# Sheet1.net
KiCad netlist of a schematic drawn in Altium Designer
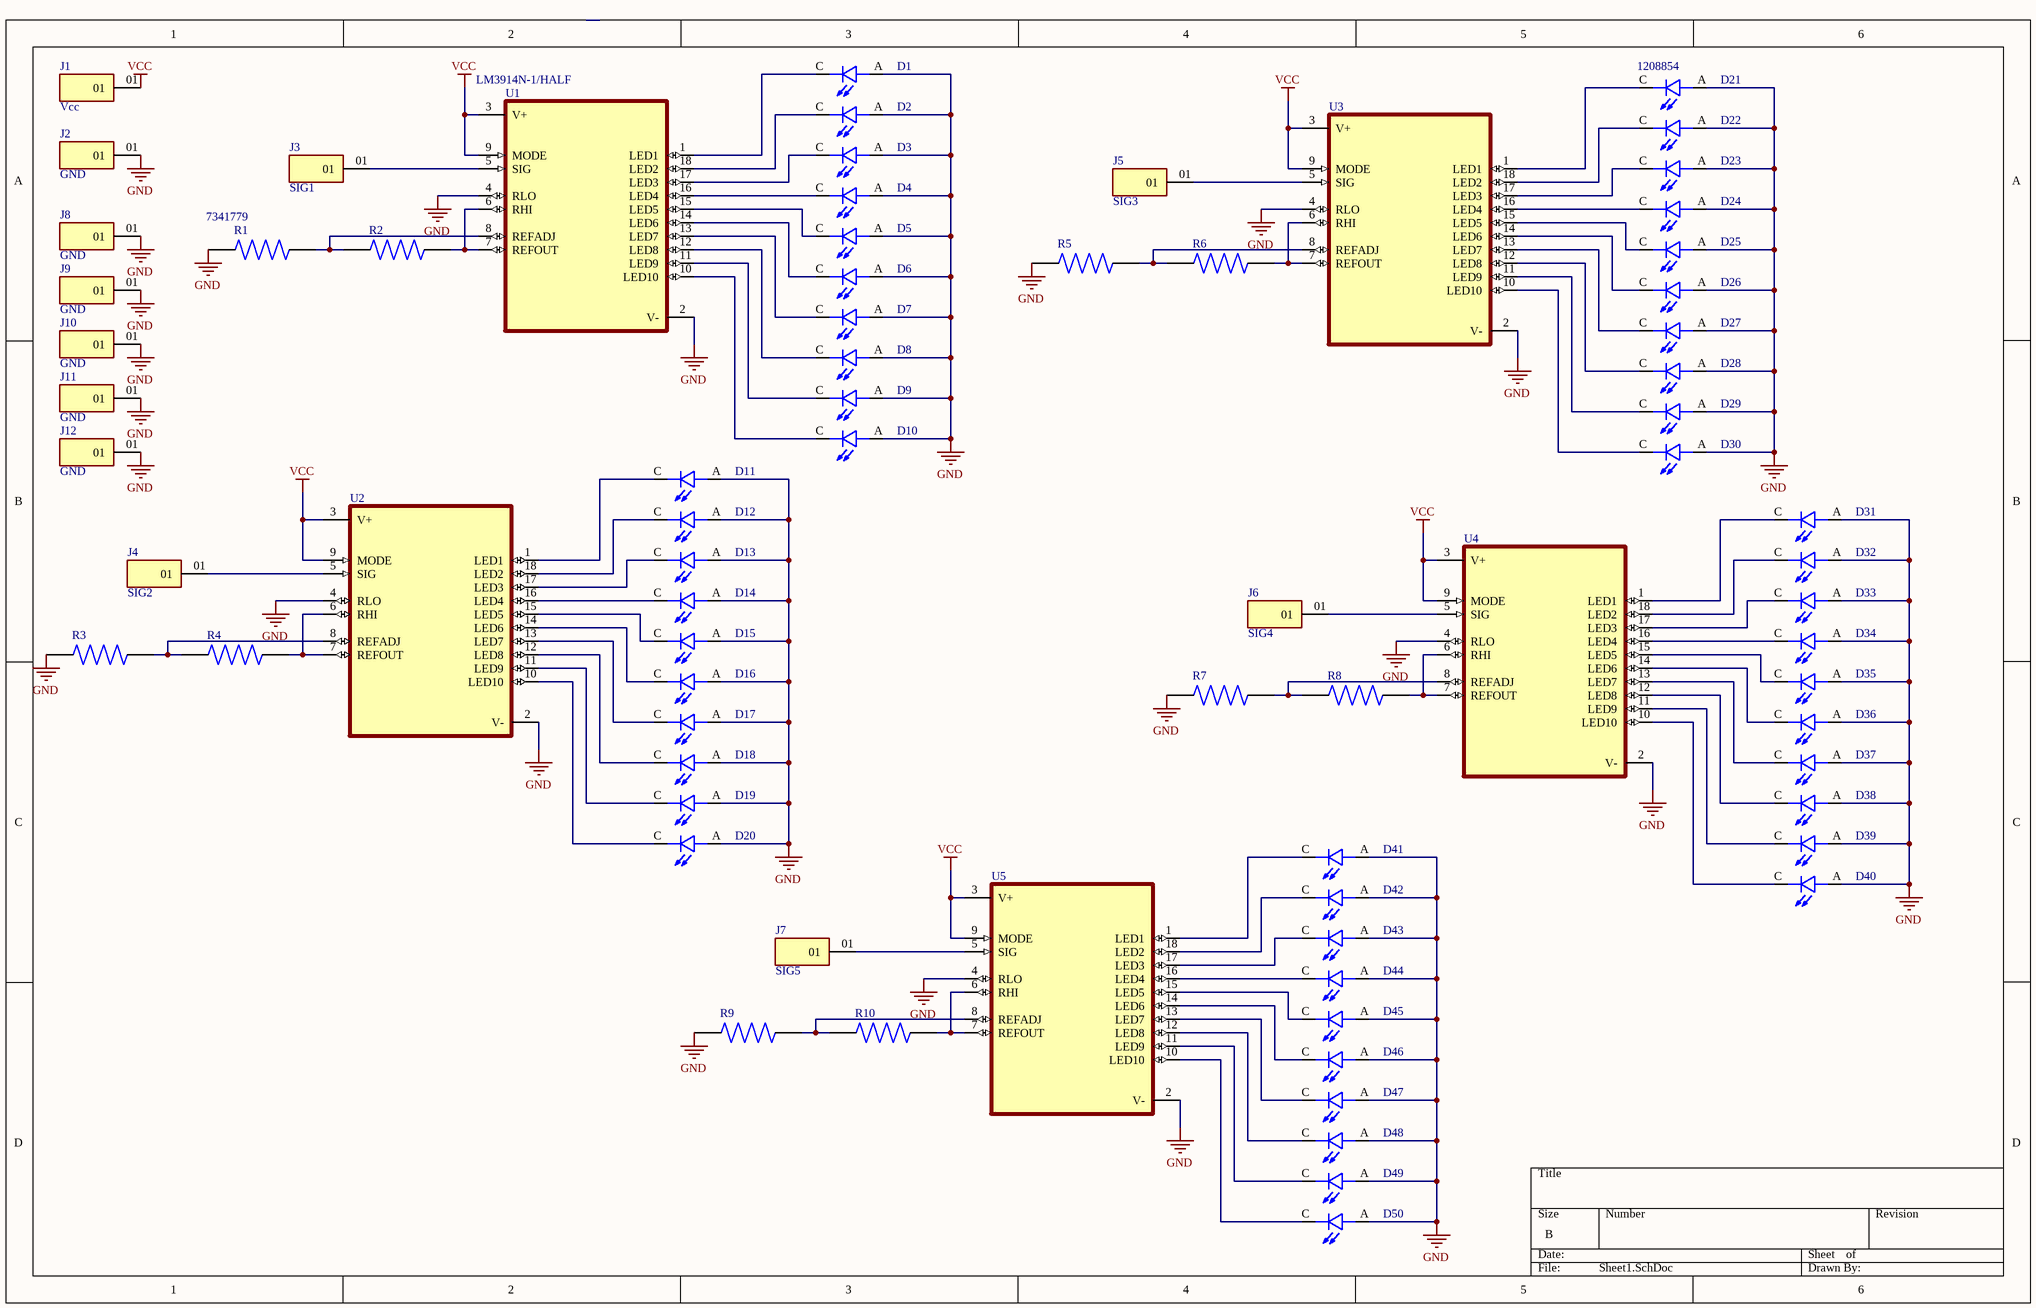
[diagram p0: Sheet1.SchDoc]

(export (version "E")
  (design (tool "Eeschema 10.0.6"))
  (components
    (comp (ref "D1")
      (value "L08R5000Q1")
      (footprint "LEDRD254W57D500H1070")
      (description "LED, Orange, Through Hole, T-1 3/4 (5mm), 30 mA, 2.1 V, 635 nm")
      (libsource (lib "L08R5000Q1") (part "L08R5000Q1"))
    )
    (comp (ref "D2")
      (value "L08R5000Q1")
      (footprint "LEDRD254W57D500H1070")
      (description "LED, Orange, Through Hole, T-1 3/4 (5mm), 30 mA, 2.1 V, 635 nm")
      (libsource (lib "L08R5000Q1") (part "L08R5000Q1"))
    )
    (comp (ref "D3")
      (value "L08R5000Q1")
      (footprint "LEDRD254W57D500H1070")
      (description "LED, Orange, Through Hole, T-1 3/4 (5mm), 30 mA, 2.1 V, 635 nm")
      (libsource (lib "L08R5000Q1") (part "L08R5000Q1"))
    )
    (comp (ref "D4")
      (value "L08R5000Q1")
      (footprint "LEDRD254W57D500H1070")
      (description "LED, Orange, Through Hole, T-1 3/4 (5mm), 30 mA, 2.1 V, 635 nm")
      (libsource (lib "L08R5000Q1") (part "L08R5000Q1"))
    )
    (comp (ref "D5")
      (value "L08R5000Q1")
      (footprint "LEDRD254W57D500H1070")
      (description "LED, Orange, Through Hole, T-1 3/4 (5mm), 30 mA, 2.1 V, 635 nm")
      (libsource (lib "L08R5000Q1") (part "L08R5000Q1"))
    )
    (comp (ref "D6")
      (value "L08R5000Q1")
      (footprint "LEDRD254W57D500H1070")
      (description "LED, Orange, Through Hole, T-1 3/4 (5mm), 30 mA, 2.1 V, 635 nm")
      (libsource (lib "L08R5000Q1") (part "L08R5000Q1"))
    )
    (comp (ref "D7")
      (value "L08R5000Q1")
      (footprint "LEDRD254W57D500H1070")
      (description "LED, Orange, Through Hole, T-1 3/4 (5mm), 30 mA, 2.1 V, 635 nm")
      (libsource (lib "L08R5000Q1") (part "L08R5000Q1"))
    )
    (comp (ref "D8")
      (value "L08R5000Q1")
      (footprint "LEDRD254W57D500H1070")
      (description "LED, Orange, Through Hole, T-1 3/4 (5mm), 30 mA, 2.1 V, 635 nm")
      (libsource (lib "L08R5000Q1") (part "L08R5000Q1"))
    )
    (comp (ref "D9")
      (value "L08R5000Q1")
      (footprint "LEDRD254W57D500H1070")
      (description "LED, Orange, Through Hole, T-1 3/4 (5mm), 30 mA, 2.1 V, 635 nm")
      (libsource (lib "L08R5000Q1") (part "L08R5000Q1"))
    )
    (comp (ref "D10")
      (value "L08R5000Q1")
      (footprint "LEDRD254W57D500H1070")
      (description "LED, Orange, Through Hole, T-1 3/4 (5mm), 30 mA, 2.1 V, 635 nm")
      (libsource (lib "L08R5000Q1") (part "L08R5000Q1"))
    )
    (comp (ref "D11")
      (value "L08R5000Q1")
      (footprint "LEDRD254W57D500H1070")
      (description "LED, Orange, Through Hole, T-1 3/4 (5mm), 30 mA, 2.1 V, 635 nm")
      (libsource (lib "L08R5000Q1") (part "L08R5000Q1"))
    )
    (comp (ref "D12")
      (value "L08R5000Q1")
      (footprint "LEDRD254W57D500H1070")
      (description "LED, Orange, Through Hole, T-1 3/4 (5mm), 30 mA, 2.1 V, 635 nm")
      (libsource (lib "L08R5000Q1") (part "L08R5000Q1"))
    )
    (comp (ref "D13")
      (value "L08R5000Q1")
      (footprint "LEDRD254W57D500H1070")
      (description "LED, Orange, Through Hole, T-1 3/4 (5mm), 30 mA, 2.1 V, 635 nm")
      (libsource (lib "L08R5000Q1") (part "L08R5000Q1"))
    )
    (comp (ref "D14")
      (value "L08R5000Q1")
      (footprint "LEDRD254W57D500H1070")
      (description "LED, Orange, Through Hole, T-1 3/4 (5mm), 30 mA, 2.1 V, 635 nm")
      (libsource (lib "L08R5000Q1") (part "L08R5000Q1"))
    )
    (comp (ref "D15")
      (value "L08R5000Q1")
      (footprint "LEDRD254W57D500H1070")
      (description "LED, Orange, Through Hole, T-1 3/4 (5mm), 30 mA, 2.1 V, 635 nm")
      (libsource (lib "L08R5000Q1") (part "L08R5000Q1"))
    )
    (comp (ref "D16")
      (value "L08R5000Q1")
      (footprint "LEDRD254W57D500H1070")
      (description "LED, Orange, Through Hole, T-1 3/4 (5mm), 30 mA, 2.1 V, 635 nm")
      (libsource (lib "L08R5000Q1") (part "L08R5000Q1"))
    )
    (comp (ref "D17")
      (value "L08R5000Q1")
      (footprint "LEDRD254W57D500H1070")
      (description "LED, Orange, Through Hole, T-1 3/4 (5mm), 30 mA, 2.1 V, 635 nm")
      (libsource (lib "L08R5000Q1") (part "L08R5000Q1"))
    )
    (comp (ref "D18")
      (value "L08R5000Q1")
      (footprint "LEDRD254W57D500H1070")
      (description "LED, Orange, Through Hole, T-1 3/4 (5mm), 30 mA, 2.1 V, 635 nm")
      (libsource (lib "L08R5000Q1") (part "L08R5000Q1"))
    )
    (comp (ref "D19")
      (value "L08R5000Q1")
      (footprint "LEDRD254W57D500H1070")
      (description "LED, Orange, Through Hole, T-1 3/4 (5mm), 30 mA, 2.1 V, 635 nm")
      (libsource (lib "L08R5000Q1") (part "L08R5000Q1"))
    )
    (comp (ref "D20")
      (value "L08R5000Q1")
      (footprint "LEDRD254W57D500H1070")
      (description "LED, Orange, Through Hole, T-1 3/4 (5mm), 30 mA, 2.1 V, 635 nm")
      (libsource (lib "L08R5000Q1") (part "L08R5000Q1"))
    )
    (comp (ref "D21")
      (value "L08R5000Q1")
      (footprint "LEDRD254W57D500H1070")
      (description "LED, Orange, Through Hole, T-1 3/4 (5mm), 30 mA, 2.1 V, 635 nm")
      (fields (field (name "SUPPLIER PART NUMBER 1") "1208854"))
      (libsource (lib "L08R5000Q1") (part "L08R5000Q1"))
    )
    (comp (ref "D22")
      (value "L08R5000Q1")
      (footprint "LEDRD254W57D500H1070")
      (description "LED, Orange, Through Hole, T-1 3/4 (5mm), 30 mA, 2.1 V, 635 nm")
      (libsource (lib "L08R5000Q1") (part "L08R5000Q1"))
    )
    (comp (ref "D23")
      (value "L08R5000Q1")
      (footprint "LEDRD254W57D500H1070")
      (description "LED, Orange, Through Hole, T-1 3/4 (5mm), 30 mA, 2.1 V, 635 nm")
      (libsource (lib "L08R5000Q1") (part "L08R5000Q1"))
    )
    (comp (ref "D24")
      (value "L08R5000Q1")
      (footprint "LEDRD254W57D500H1070")
      (description "LED, Orange, Through Hole, T-1 3/4 (5mm), 30 mA, 2.1 V, 635 nm")
      (libsource (lib "L08R5000Q1") (part "L08R5000Q1"))
    )
    (comp (ref "D25")
      (value "L08R5000Q1")
      (footprint "LEDRD254W57D500H1070")
      (description "LED, Orange, Through Hole, T-1 3/4 (5mm), 30 mA, 2.1 V, 635 nm")
      (libsource (lib "L08R5000Q1") (part "L08R5000Q1"))
    )
    (comp (ref "D26")
      (value "L08R5000Q1")
      (footprint "LEDRD254W57D500H1070")
      (description "LED, Orange, Through Hole, T-1 3/4 (5mm), 30 mA, 2.1 V, 635 nm")
      (libsource (lib "L08R5000Q1") (part "L08R5000Q1"))
    )
    (comp (ref "D27")
      (value "L08R5000Q1")
      (footprint "LEDRD254W57D500H1070")
      (description "LED, Orange, Through Hole, T-1 3/4 (5mm), 30 mA, 2.1 V, 635 nm")
      (libsource (lib "L08R5000Q1") (part "L08R5000Q1"))
    )
    (comp (ref "D28")
      (value "L08R5000Q1")
      (footprint "LEDRD254W57D500H1070")
      (description "LED, Orange, Through Hole, T-1 3/4 (5mm), 30 mA, 2.1 V, 635 nm")
      (libsource (lib "L08R5000Q1") (part "L08R5000Q1"))
    )
    (comp (ref "D29")
      (value "L08R5000Q1")
      (footprint "LEDRD254W57D500H1070")
      (description "LED, Orange, Through Hole, T-1 3/4 (5mm), 30 mA, 2.1 V, 635 nm")
      (libsource (lib "L08R5000Q1") (part "L08R5000Q1"))
    )
    (comp (ref "D30")
      (value "L08R5000Q1")
      (footprint "LEDRD254W57D500H1070")
      (description "LED, Orange, Through Hole, T-1 3/4 (5mm), 30 mA, 2.1 V, 635 nm")
      (libsource (lib "L08R5000Q1") (part "L08R5000Q1"))
    )
    (comp (ref "D31")
      (value "L08R5000Q1")
      (footprint "LEDRD254W57D500H1070")
      (description "LED, Orange, Through Hole, T-1 3/4 (5mm), 30 mA, 2.1 V, 635 nm")
      (libsource (lib "L08R5000Q1") (part "L08R5000Q1"))
    )
    (comp (ref "D32")
      (value "L08R5000Q1")
      (footprint "LEDRD254W57D500H1070")
      (description "LED, Orange, Through Hole, T-1 3/4 (5mm), 30 mA, 2.1 V, 635 nm")
      (libsource (lib "L08R5000Q1") (part "L08R5000Q1"))
    )
    (comp (ref "D33")
      (value "L08R5000Q1")
      (footprint "LEDRD254W57D500H1070")
      (description "LED, Orange, Through Hole, T-1 3/4 (5mm), 30 mA, 2.1 V, 635 nm")
      (libsource (lib "L08R5000Q1") (part "L08R5000Q1"))
    )
    (comp (ref "D34")
      (value "L08R5000Q1")
      (footprint "LEDRD254W57D500H1070")
      (description "LED, Orange, Through Hole, T-1 3/4 (5mm), 30 mA, 2.1 V, 635 nm")
      (libsource (lib "L08R5000Q1") (part "L08R5000Q1"))
    )
    (comp (ref "D35")
      (value "L08R5000Q1")
      (footprint "LEDRD254W57D500H1070")
      (description "LED, Orange, Through Hole, T-1 3/4 (5mm), 30 mA, 2.1 V, 635 nm")
      (libsource (lib "L08R5000Q1") (part "L08R5000Q1"))
    )
    (comp (ref "D36")
      (value "L08R5000Q1")
      (footprint "LEDRD254W57D500H1070")
      (description "LED, Orange, Through Hole, T-1 3/4 (5mm), 30 mA, 2.1 V, 635 nm")
      (libsource (lib "L08R5000Q1") (part "L08R5000Q1"))
    )
    (comp (ref "D37")
      (value "L08R5000Q1")
      (footprint "LEDRD254W57D500H1070")
      (description "LED, Orange, Through Hole, T-1 3/4 (5mm), 30 mA, 2.1 V, 635 nm")
      (libsource (lib "L08R5000Q1") (part "L08R5000Q1"))
    )
    (comp (ref "D38")
      (value "L08R5000Q1")
      (footprint "LEDRD254W57D500H1070")
      (description "LED, Orange, Through Hole, T-1 3/4 (5mm), 30 mA, 2.1 V, 635 nm")
      (libsource (lib "L08R5000Q1") (part "L08R5000Q1"))
    )
    (comp (ref "D39")
      (value "L08R5000Q1")
      (footprint "LEDRD254W57D500H1070")
      (description "LED, Orange, Through Hole, T-1 3/4 (5mm), 30 mA, 2.1 V, 635 nm")
      (libsource (lib "L08R5000Q1") (part "L08R5000Q1"))
    )
    (comp (ref "D40")
      (value "L08R5000Q1")
      (footprint "LEDRD254W57D500H1070")
      (description "LED, Orange, Through Hole, T-1 3/4 (5mm), 30 mA, 2.1 V, 635 nm")
      (libsource (lib "L08R5000Q1") (part "L08R5000Q1"))
    )
    (comp (ref "D41")
      (value "L08R5000Q1")
      (footprint "LEDRD254W57D500H1070")
      (description "LED, Orange, Through Hole, T-1 3/4 (5mm), 30 mA, 2.1 V, 635 nm")
      (libsource (lib "L08R5000Q1") (part "L08R5000Q1"))
    )
    (comp (ref "D42")
      (value "L08R5000Q1")
      (footprint "LEDRD254W57D500H1070")
      (description "LED, Orange, Through Hole, T-1 3/4 (5mm), 30 mA, 2.1 V, 635 nm")
      (libsource (lib "L08R5000Q1") (part "L08R5000Q1"))
    )
    (comp (ref "D43")
      (value "L08R5000Q1")
      (footprint "LEDRD254W57D500H1070")
      (description "LED, Orange, Through Hole, T-1 3/4 (5mm), 30 mA, 2.1 V, 635 nm")
      (libsource (lib "L08R5000Q1") (part "L08R5000Q1"))
    )
    (comp (ref "D44")
      (value "L08R5000Q1")
      (footprint "LEDRD254W57D500H1070")
      (description "LED, Orange, Through Hole, T-1 3/4 (5mm), 30 mA, 2.1 V, 635 nm")
      (libsource (lib "L08R5000Q1") (part "L08R5000Q1"))
    )
    (comp (ref "D45")
      (value "L08R5000Q1")
      (footprint "LEDRD254W57D500H1070")
      (description "LED, Orange, Through Hole, T-1 3/4 (5mm), 30 mA, 2.1 V, 635 nm")
      (libsource (lib "L08R5000Q1") (part "L08R5000Q1"))
    )
    (comp (ref "D46")
      (value "L08R5000Q1")
      (footprint "LEDRD254W57D500H1070")
      (description "LED, Orange, Through Hole, T-1 3/4 (5mm), 30 mA, 2.1 V, 635 nm")
      (libsource (lib "L08R5000Q1") (part "L08R5000Q1"))
    )
    (comp (ref "D47")
      (value "L08R5000Q1")
      (footprint "LEDRD254W57D500H1070")
      (description "LED, Orange, Through Hole, T-1 3/4 (5mm), 30 mA, 2.1 V, 635 nm")
      (libsource (lib "L08R5000Q1") (part "L08R5000Q1"))
    )
    (comp (ref "D48")
      (value "L08R5000Q1")
      (footprint "LEDRD254W57D500H1070")
      (description "LED, Orange, Through Hole, T-1 3/4 (5mm), 30 mA, 2.1 V, 635 nm")
      (libsource (lib "L08R5000Q1") (part "L08R5000Q1"))
    )
    (comp (ref "D49")
      (value "L08R5000Q1")
      (footprint "LEDRD254W57D500H1070")
      (description "LED, Orange, Through Hole, T-1 3/4 (5mm), 30 mA, 2.1 V, 635 nm")
      (libsource (lib "L08R5000Q1") (part "L08R5000Q1"))
    )
    (comp (ref "D50")
      (value "L08R5000Q1")
      (footprint "LEDRD254W57D500H1070")
      (description "LED, Orange, Through Hole, T-1 3/4 (5mm), 30 mA, 2.1 V, 635 nm")
      (libsource (lib "L08R5000Q1") (part "L08R5000Q1"))
    )
    (comp (ref "J1")
      (value "Vcc")
      (footprint "SAMTEC_MTMM-101-XX-X-S-XXX")
      (description "Connector Header position")
      (fields (field (name "MP") "MTMM-101-XX-X-S-XXX"))
      (libsource (lib "MTMM-101-XX-X-S-XXX") (part "MTMM-101-XX-X-S-XXX"))
    )
    (comp (ref "J2")
      (value "GND")
      (footprint "SAMTEC_MTMM-101-XX-X-S-XXX")
      (description "Connector Header position")
      (fields (field (name "MP") "MTMM-101-XX-X-S-XXX"))
      (libsource (lib "MTMM-101-XX-X-S-XXX") (part "MTMM-101-XX-X-S-XXX"))
    )
    (comp (ref "J3")
      (value "SIG1")
      (footprint "SAMTEC_MTMM-101-XX-X-S-XXX")
      (description "Connector Header position")
      (fields (field (name "MP") "MTMM-101-XX-X-S-XXX"))
      (libsource (lib "MTMM-101-XX-X-S-XXX") (part "MTMM-101-XX-X-S-XXX"))
    )
    (comp (ref "J4")
      (value "SIG2")
      (footprint "SAMTEC_MTMM-101-XX-X-S-XXX")
      (description "Connector Header position")
      (fields (field (name "MP") "MTMM-101-XX-X-S-XXX"))
      (libsource (lib "MTMM-101-XX-X-S-XXX") (part "MTMM-101-XX-X-S-XXX"))
    )
    (comp (ref "J5")
      (value "SIG3")
      (footprint "SAMTEC_MTMM-101-XX-X-S-XXX")
      (description "Connector Header position")
      (fields (field (name "MP") "MTMM-101-XX-X-S-XXX"))
      (libsource (lib "MTMM-101-XX-X-S-XXX") (part "MTMM-101-XX-X-S-XXX"))
    )
    (comp (ref "J6")
      (value "SIG4")
      (footprint "SAMTEC_MTMM-101-XX-X-S-XXX")
      (description "Connector Header position")
      (fields (field (name "MP") "MTMM-101-XX-X-S-XXX"))
      (libsource (lib "MTMM-101-XX-X-S-XXX") (part "MTMM-101-XX-X-S-XXX"))
    )
    (comp (ref "J7")
      (value "SIG5")
      (footprint "SAMTEC_MTMM-101-XX-X-S-XXX")
      (description "Connector Header position")
      (fields (field (name "MP") "MTMM-101-XX-X-S-XXX"))
      (libsource (lib "MTMM-101-XX-X-S-XXX") (part "MTMM-101-XX-X-S-XXX"))
    )
    (comp (ref "J8")
      (value "GND")
      (footprint "SAMTEC_MTMM-101-XX-X-S-XXX")
      (description "Connector Header position")
      (fields (field (name "MP") "MTMM-101-XX-X-S-XXX"))
      (libsource (lib "MTMM-101-XX-X-S-XXX") (part "MTMM-101-XX-X-S-XXX"))
    )
    (comp (ref "J9")
      (value "GND")
      (footprint "SAMTEC_MTMM-101-XX-X-S-XXX")
      (description "Connector Header position")
      (fields (field (name "MP") "MTMM-101-XX-X-S-XXX"))
      (libsource (lib "MTMM-101-XX-X-S-XXX") (part "MTMM-101-XX-X-S-XXX"))
    )
    (comp (ref "J10")
      (value "GND")
      (footprint "SAMTEC_MTMM-101-XX-X-S-XXX")
      (description "Connector Header position")
      (fields (field (name "MP") "MTMM-101-XX-X-S-XXX"))
      (libsource (lib "MTMM-101-XX-X-S-XXX") (part "MTMM-101-XX-X-S-XXX"))
    )
    (comp (ref "J11")
      (value "GND")
      (footprint "SAMTEC_MTMM-101-XX-X-S-XXX")
      (description "Connector Header position")
      (fields (field (name "MP") "MTMM-101-XX-X-S-XXX"))
      (libsource (lib "MTMM-101-XX-X-S-XXX") (part "MTMM-101-XX-X-S-XXX"))
    )
    (comp (ref "J12")
      (value "GND")
      (footprint "SAMTEC_MTMM-101-XX-X-S-XXX")
      (description "Connector Header position")
      (fields (field (name "MP") "MTMM-101-XX-X-S-XXX"))
      (libsource (lib "MTMM-101-XX-X-S-XXX") (part "MTMM-101-XX-X-S-XXX"))
    )
    (comp (ref "R1")
      (value "MFR-25FBF52-1K")
      (footprint "RESAD1100W55L680D260")
      (description "1.78 kOhms Â±1% 0.25W, 1/4W Through Hole Resistor Axial - Metal Film")
      (fields (field (name "MF") "Yageo") (field (name "SUPPLIER PART NUMBER 1") "7341779"))
      (libsource (lib "MFR-25FBF52-1K") (part "MFR-25FBF52-1K"))
    )
    (comp (ref "R2")
      (value "MFR-25FBF52-1K")
      (footprint "RESAD1100W55L680D260")
      (description "1.78 kOhms Â±1% 0.25W, 1/4W Through Hole Resistor Axial - Metal Film")
      (fields (field (name "MF") "Yageo"))
      (libsource (lib "MFR-25FBF52-1K") (part "MFR-25FBF52-1K"))
    )
    (comp (ref "R3")
      (value "MFR-25FBF52-1K")
      (footprint "RESAD1100W55L680D260")
      (description "1.78 kOhms Â±1% 0.25W, 1/4W Through Hole Resistor Axial - Metal Film")
      (fields (field (name "MF") "Yageo"))
      (libsource (lib "MFR-25FBF52-1K") (part "MFR-25FBF52-1K"))
    )
    (comp (ref "R4")
      (value "MFR-25FBF52-1K")
      (footprint "RESAD1100W55L680D260")
      (description "1.78 kOhms Â±1% 0.25W, 1/4W Through Hole Resistor Axial - Metal Film")
      (fields (field (name "MF") "Yageo"))
      (libsource (lib "MFR-25FBF52-1K") (part "MFR-25FBF52-1K"))
    )
    (comp (ref "R5")
      (value "MFR-25FBF52-1K")
      (footprint "RESAD1100W55L680D260")
      (description "1.78 kOhms Â±1% 0.25W, 1/4W Through Hole Resistor Axial - Metal Film")
      (fields (field (name "MF") "Yageo"))
      (libsource (lib "MFR-25FBF52-1K") (part "MFR-25FBF52-1K"))
    )
    (comp (ref "R6")
      (value "MFR-25FBF52-1K")
      (footprint "RESAD1100W55L680D260")
      (description "1.78 kOhms Â±1% 0.25W, 1/4W Through Hole Resistor Axial - Metal Film")
      (fields (field (name "MF") "Yageo"))
      (libsource (lib "MFR-25FBF52-1K") (part "MFR-25FBF52-1K"))
    )
    (comp (ref "R7")
      (value "MFR-25FBF52-1K")
      (footprint "RESAD1100W55L680D260")
      (description "1.78 kOhms Â±1% 0.25W, 1/4W Through Hole Resistor Axial - Metal Film")
      (fields (field (name "MF") "Yageo"))
      (libsource (lib "MFR-25FBF52-1K") (part "MFR-25FBF52-1K"))
    )
    (comp (ref "R8")
      (value "MFR-25FBF52-1K")
      (footprint "RESAD1100W55L680D260")
      (description "1.78 kOhms Â±1% 0.25W, 1/4W Through Hole Resistor Axial - Metal Film")
      (fields (field (name "MF") "Yageo"))
      (libsource (lib "MFR-25FBF52-1K") (part "MFR-25FBF52-1K"))
    )
    (comp (ref "R9")
      (value "MFR-25FBF52-1K")
      (footprint "RESAD1100W55L680D260")
      (description "1.78 kOhms Â±1% 0.25W, 1/4W Through Hole Resistor Axial - Metal Film")
      (fields (field (name "MF") "Yageo"))
      (libsource (lib "MFR-25FBF52-1K") (part "MFR-25FBF52-1K"))
    )
    (comp (ref "R10")
      (value "MFR-25FBF52-1K")
      (footprint "RESAD1100W55L680D260")
      (description "1.78 kOhms Â±1% 0.25W, 1/4W Through Hole Resistor Axial - Metal Film")
      (fields (field (name "MF") "Yageo"))
      (libsource (lib "MFR-25FBF52-1K") (part "MFR-25FBF52-1K"))
    )
    (comp (ref "U1")
      (value "LM3914N-1")
      (footprint "DIP952W45P254L2336H533Q18")
      (fields (field (name "SUPPLIER PART NUMBER 1") "LM3914N-1/HALF"))
      (libsource (lib "LM3914N-1") (part "LM3914N-1"))
    )
    (comp (ref "U2")
      (value "LM3914N-1")
      (footprint "DIP952W45P254L2336H533Q18")
      (libsource (lib "LM3914N-1") (part "LM3914N-1"))
    )
    (comp (ref "U3")
      (value "LM3914N-1")
      (footprint "DIP952W45P254L2336H533Q18")
      (libsource (lib "LM3914N-1") (part "LM3914N-1"))
    )
    (comp (ref "U4")
      (value "LM3914N-1")
      (footprint "DIP952W45P254L2336H533Q18")
      (libsource (lib "LM3914N-1") (part "LM3914N-1"))
    )
    (comp (ref "U5")
      (value "LM3914N-1")
      (footprint "DIP952W45P254L2336H533Q18")
      (libsource (lib "LM3914N-1") (part "LM3914N-1"))
    )
  )
  (nets
    (net (code "1") (name "GND") (class "Default")
      (node (ref "D1") (pin "A") (pinfunction "A_A") (pintype "passive"))
      (node (ref "D10") (pin "A") (pinfunction "A_A") (pintype "passive"))
      (node (ref "D11") (pin "A") (pinfunction "A_A") (pintype "passive"))
      (node (ref "D12") (pin "A") (pinfunction "A_A") (pintype "passive"))
      (node (ref "D13") (pin "A") (pinfunction "A_A") (pintype "passive"))
      (node (ref "D14") (pin "A") (pinfunction "A_A") (pintype "passive"))
      (node (ref "D15") (pin "A") (pinfunction "A_A") (pintype "passive"))
      (node (ref "D16") (pin "A") (pinfunction "A_A") (pintype "passive"))
      (node (ref "D17") (pin "A") (pinfunction "A_A") (pintype "passive"))
      (node (ref "D18") (pin "A") (pinfunction "A_A") (pintype "passive"))
      (node (ref "D19") (pin "A") (pinfunction "A_A") (pintype "passive"))
      (node (ref "D2") (pin "A") (pinfunction "A_A") (pintype "passive"))
      (node (ref "D20") (pin "A") (pinfunction "A_A") (pintype "passive"))
      (node (ref "D21") (pin "A") (pinfunction "A_A") (pintype "passive"))
      (node (ref "D22") (pin "A") (pinfunction "A_A") (pintype "passive"))
      (node (ref "D23") (pin "A") (pinfunction "A_A") (pintype "passive"))
      (node (ref "D24") (pin "A") (pinfunction "A_A") (pintype "passive"))
      (node (ref "D25") (pin "A") (pinfunction "A_A") (pintype "passive"))
      (node (ref "D26") (pin "A") (pinfunction "A_A") (pintype "passive"))
      (node (ref "D27") (pin "A") (pinfunction "A_A") (pintype "passive"))
      (node (ref "D28") (pin "A") (pinfunction "A_A") (pintype "passive"))
      (node (ref "D29") (pin "A") (pinfunction "A_A") (pintype "passive"))
      (node (ref "D3") (pin "A") (pinfunction "A_A") (pintype "passive"))
      (node (ref "D30") (pin "A") (pinfunction "A_A") (pintype "passive"))
      (node (ref "D31") (pin "A") (pinfunction "A_A") (pintype "passive"))
      (node (ref "D32") (pin "A") (pinfunction "A_A") (pintype "passive"))
      (node (ref "D33") (pin "A") (pinfunction "A_A") (pintype "passive"))
      (node (ref "D34") (pin "A") (pinfunction "A_A") (pintype "passive"))
      (node (ref "D35") (pin "A") (pinfunction "A_A") (pintype "passive"))
      (node (ref "D36") (pin "A") (pinfunction "A_A") (pintype "passive"))
      (node (ref "D37") (pin "A") (pinfunction "A_A") (pintype "passive"))
      (node (ref "D38") (pin "A") (pinfunction "A_A") (pintype "passive"))
      (node (ref "D39") (pin "A") (pinfunction "A_A") (pintype "passive"))
      (node (ref "D4") (pin "A") (pinfunction "A_A") (pintype "passive"))
      (node (ref "D40") (pin "A") (pinfunction "A_A") (pintype "passive"))
      (node (ref "D41") (pin "A") (pinfunction "A_A") (pintype "passive"))
      (node (ref "D42") (pin "A") (pinfunction "A_A") (pintype "passive"))
      (node (ref "D43") (pin "A") (pinfunction "A_A") (pintype "passive"))
      (node (ref "D44") (pin "A") (pinfunction "A_A") (pintype "passive"))
      (node (ref "D45") (pin "A") (pinfunction "A_A") (pintype "passive"))
      (node (ref "D46") (pin "A") (pinfunction "A_A") (pintype "passive"))
      (node (ref "D47") (pin "A") (pinfunction "A_A") (pintype "passive"))
      (node (ref "D48") (pin "A") (pinfunction "A_A") (pintype "passive"))
      (node (ref "D49") (pin "A") (pinfunction "A_A") (pintype "passive"))
      (node (ref "D5") (pin "A") (pinfunction "A_A") (pintype "passive"))
      (node (ref "D50") (pin "A") (pinfunction "A_A") (pintype "passive"))
      (node (ref "D6") (pin "A") (pinfunction "A_A") (pintype "passive"))
      (node (ref "D7") (pin "A") (pinfunction "A_A") (pintype "passive"))
      (node (ref "D8") (pin "A") (pinfunction "A_A") (pintype "passive"))
      (node (ref "D9") (pin "A") (pinfunction "A_A") (pintype "passive"))
      (node (ref "J10") (pin "01") (pinfunction "01_01") (pintype "passive"))
      (node (ref "J11") (pin "01") (pinfunction "01_01") (pintype "passive"))
      (node (ref "J12") (pin "01") (pinfunction "01_01") (pintype "passive"))
      (node (ref "J2") (pin "01") (pinfunction "01_01") (pintype "passive"))
      (node (ref "J8") (pin "01") (pinfunction "01_01") (pintype "passive"))
      (node (ref "J9") (pin "01") (pinfunction "01_01") (pintype "passive"))
      (node (ref "R1") (pin "1") (pinfunction "1_1") (pintype "passive"))
      (node (ref "R3") (pin "1") (pinfunction "1_1") (pintype "passive"))
      (node (ref "R5") (pin "1") (pinfunction "1_1") (pintype "passive"))
      (node (ref "R7") (pin "1") (pinfunction "1_1") (pintype "passive"))
      (node (ref "R9") (pin "1") (pinfunction "1_1") (pintype "passive"))
      (node (ref "U1") (pin "2") (pinfunction "V-_2") (pintype "power_in"))
      (node (ref "U1") (pin "4") (pinfunction "RLO_4") (pintype "bidirectional"))
      (node (ref "U2") (pin "2") (pinfunction "V-_2") (pintype "power_in"))
      (node (ref "U2") (pin "4") (pinfunction "RLO_4") (pintype "bidirectional"))
      (node (ref "U3") (pin "2") (pinfunction "V-_2") (pintype "power_in"))
      (node (ref "U3") (pin "4") (pinfunction "RLO_4") (pintype "bidirectional"))
      (node (ref "U4") (pin "2") (pinfunction "V-_2") (pintype "power_in"))
      (node (ref "U4") (pin "4") (pinfunction "RLO_4") (pintype "bidirectional"))
      (node (ref "U5") (pin "2") (pinfunction "V-_2") (pintype "power_in"))
      (node (ref "U5") (pin "4") (pinfunction "RLO_4") (pintype "bidirectional"))
    )
    (net (code "2") (name "Net-(U1-LED1)") (class "Default")
      (node (ref "D1") (pin "C") (pinfunction "C_C") (pintype "passive"))
      (node (ref "U1") (pin "1") (pinfunction "LED1_1") (pintype "bidirectional"))
    )
    (net (code "3") (name "Net-(U1-LED2)") (class "Default")
      (node (ref "D2") (pin "C") (pinfunction "C_C") (pintype "passive"))
      (node (ref "U1") (pin "18") (pinfunction "LED2_18") (pintype "bidirectional"))
    )
    (net (code "4") (name "Net-(U1-LED3)") (class "Default")
      (node (ref "D3") (pin "C") (pinfunction "C_C") (pintype "passive"))
      (node (ref "U1") (pin "17") (pinfunction "LED3_17") (pintype "bidirectional"))
    )
    (net (code "5") (name "Net-(U1-LED4)") (class "Default")
      (node (ref "D4") (pin "C") (pinfunction "C_C") (pintype "passive"))
      (node (ref "U1") (pin "16") (pinfunction "LED4_16") (pintype "bidirectional"))
    )
    (net (code "6") (name "Net-(U1-LED5)") (class "Default")
      (node (ref "D5") (pin "C") (pinfunction "C_C") (pintype "passive"))
      (node (ref "U1") (pin "15") (pinfunction "LED5_15") (pintype "bidirectional"))
    )
    (net (code "7") (name "Net-(U1-LED6)") (class "Default")
      (node (ref "D6") (pin "C") (pinfunction "C_C") (pintype "passive"))
      (node (ref "U1") (pin "14") (pinfunction "LED6_14") (pintype "bidirectional"))
    )
    (net (code "8") (name "Net-(U1-LED7)") (class "Default")
      (node (ref "D7") (pin "C") (pinfunction "C_C") (pintype "passive"))
      (node (ref "U1") (pin "13") (pinfunction "LED7_13") (pintype "bidirectional"))
    )
    (net (code "9") (name "Net-(U1-LED8)") (class "Default")
      (node (ref "D8") (pin "C") (pinfunction "C_C") (pintype "passive"))
      (node (ref "U1") (pin "12") (pinfunction "LED8_12") (pintype "bidirectional"))
    )
    (net (code "10") (name "Net-(U1-LED9)") (class "Default")
      (node (ref "D9") (pin "C") (pinfunction "C_C") (pintype "passive"))
      (node (ref "U1") (pin "11") (pinfunction "LED9_11") (pintype "bidirectional"))
    )
    (net (code "11") (name "Net-(U1-LED10)") (class "Default")
      (node (ref "D10") (pin "C") (pinfunction "C_C") (pintype "passive"))
      (node (ref "U1") (pin "10") (pinfunction "LED10_10") (pintype "bidirectional"))
    )
    (net (code "12") (name "Net-(U1-REFADJ)") (class "Default")
      (node (ref "R1") (pin "2") (pinfunction "2_2") (pintype "passive"))
      (node (ref "R2") (pin "1") (pinfunction "1_1") (pintype "passive"))
      (node (ref "U1") (pin "8") (pinfunction "REFADJ_8") (pintype "bidirectional"))
    )
    (net (code "13") (name "Net-(U1-REFOUT)") (class "Default")
      (node (ref "R2") (pin "2") (pinfunction "2_2") (pintype "passive"))
      (node (ref "U1") (pin "6") (pinfunction "RHI_6") (pintype "bidirectional"))
      (node (ref "U1") (pin "7") (pinfunction "REFOUT_7") (pintype "bidirectional"))
    )
    (net (code "14") (name "Net-(U1-SIG)") (class "Default")
      (node (ref "J3") (pin "01") (pinfunction "01_01") (pintype "passive"))
      (node (ref "U1") (pin "5") (pinfunction "SIG_5") (pintype "input"))
    )
    (net (code "15") (name "Net-(U2-LED1)") (class "Default")
      (node (ref "D11") (pin "C") (pinfunction "C_C") (pintype "passive"))
      (node (ref "U2") (pin "1") (pinfunction "LED1_1") (pintype "bidirectional"))
    )
    (net (code "16") (name "Net-(U2-LED2)") (class "Default")
      (node (ref "D12") (pin "C") (pinfunction "C_C") (pintype "passive"))
      (node (ref "U2") (pin "18") (pinfunction "LED2_18") (pintype "bidirectional"))
    )
    (net (code "17") (name "Net-(U2-LED3)") (class "Default")
      (node (ref "D13") (pin "C") (pinfunction "C_C") (pintype "passive"))
      (node (ref "U2") (pin "17") (pinfunction "LED3_17") (pintype "bidirectional"))
    )
    (net (code "18") (name "Net-(U2-LED4)") (class "Default")
      (node (ref "D14") (pin "C") (pinfunction "C_C") (pintype "passive"))
      (node (ref "U2") (pin "16") (pinfunction "LED4_16") (pintype "bidirectional"))
    )
    (net (code "19") (name "Net-(U2-LED5)") (class "Default")
      (node (ref "D15") (pin "C") (pinfunction "C_C") (pintype "passive"))
      (node (ref "U2") (pin "15") (pinfunction "LED5_15") (pintype "bidirectional"))
    )
    (net (code "20") (name "Net-(U2-LED6)") (class "Default")
      (node (ref "D16") (pin "C") (pinfunction "C_C") (pintype "passive"))
      (node (ref "U2") (pin "14") (pinfunction "LED6_14") (pintype "bidirectional"))
    )
    (net (code "21") (name "Net-(U2-LED7)") (class "Default")
      (node (ref "D17") (pin "C") (pinfunction "C_C") (pintype "passive"))
      (node (ref "U2") (pin "13") (pinfunction "LED7_13") (pintype "bidirectional"))
    )
    (net (code "22") (name "Net-(U2-LED8)") (class "Default")
      (node (ref "D18") (pin "C") (pinfunction "C_C") (pintype "passive"))
      (node (ref "U2") (pin "12") (pinfunction "LED8_12") (pintype "bidirectional"))
    )
    (net (code "23") (name "Net-(U2-LED9)") (class "Default")
      (node (ref "D19") (pin "C") (pinfunction "C_C") (pintype "passive"))
      (node (ref "U2") (pin "11") (pinfunction "LED9_11") (pintype "bidirectional"))
    )
    (net (code "24") (name "Net-(U2-LED10)") (class "Default")
      (node (ref "D20") (pin "C") (pinfunction "C_C") (pintype "passive"))
      (node (ref "U2") (pin "10") (pinfunction "LED10_10") (pintype "bidirectional"))
    )
    (net (code "25") (name "Net-(U2-REFADJ)") (class "Default")
      (node (ref "R3") (pin "2") (pinfunction "2_2") (pintype "passive"))
      (node (ref "R4") (pin "1") (pinfunction "1_1") (pintype "passive"))
      (node (ref "U2") (pin "8") (pinfunction "REFADJ_8") (pintype "bidirectional"))
    )
    (net (code "26") (name "Net-(U2-REFOUT)") (class "Default")
      (node (ref "R4") (pin "2") (pinfunction "2_2") (pintype "passive"))
      (node (ref "U2") (pin "6") (pinfunction "RHI_6") (pintype "bidirectional"))
      (node (ref "U2") (pin "7") (pinfunction "REFOUT_7") (pintype "bidirectional"))
    )
    (net (code "27") (name "Net-(U2-SIG)") (class "Default")
      (node (ref "J4") (pin "01") (pinfunction "01_01") (pintype "passive"))
      (node (ref "U2") (pin "5") (pinfunction "SIG_5") (pintype "input"))
    )
    (net (code "28") (name "Net-(U3-LED1)") (class "Default")
      (node (ref "D21") (pin "C") (pinfunction "C_C") (pintype "passive"))
      (node (ref "U3") (pin "1") (pinfunction "LED1_1") (pintype "bidirectional"))
    )
    (net (code "29") (name "Net-(U3-LED2)") (class "Default")
      (node (ref "D22") (pin "C") (pinfunction "C_C") (pintype "passive"))
      (node (ref "U3") (pin "18") (pinfunction "LED2_18") (pintype "bidirectional"))
    )
    (net (code "30") (name "Net-(U3-LED3)") (class "Default")
      (node (ref "D23") (pin "C") (pinfunction "C_C") (pintype "passive"))
      (node (ref "U3") (pin "17") (pinfunction "LED3_17") (pintype "bidirectional"))
    )
    (net (code "31") (name "Net-(U3-LED4)") (class "Default")
      (node (ref "D24") (pin "C") (pinfunction "C_C") (pintype "passive"))
      (node (ref "U3") (pin "16") (pinfunction "LED4_16") (pintype "bidirectional"))
    )
    (net (code "32") (name "Net-(U3-LED5)") (class "Default")
      (node (ref "D25") (pin "C") (pinfunction "C_C") (pintype "passive"))
      (node (ref "U3") (pin "15") (pinfunction "LED5_15") (pintype "bidirectional"))
    )
    (net (code "33") (name "Net-(U3-LED6)") (class "Default")
      (node (ref "D26") (pin "C") (pinfunction "C_C") (pintype "passive"))
      (node (ref "U3") (pin "14") (pinfunction "LED6_14") (pintype "bidirectional"))
    )
    (net (code "34") (name "Net-(U3-LED7)") (class "Default")
      (node (ref "D27") (pin "C") (pinfunction "C_C") (pintype "passive"))
      (node (ref "U3") (pin "13") (pinfunction "LED7_13") (pintype "bidirectional"))
    )
    (net (code "35") (name "Net-(U3-LED8)") (class "Default")
      (node (ref "D28") (pin "C") (pinfunction "C_C") (pintype "passive"))
      (node (ref "U3") (pin "12") (pinfunction "LED8_12") (pintype "bidirectional"))
    )
    (net (code "36") (name "Net-(U3-LED9)") (class "Default")
      (node (ref "D29") (pin "C") (pinfunction "C_C") (pintype "passive"))
      (node (ref "U3") (pin "11") (pinfunction "LED9_11") (pintype "bidirectional"))
    )
    (net (code "37") (name "Net-(U3-LED10)") (class "Default")
      (node (ref "D30") (pin "C") (pinfunction "C_C") (pintype "passive"))
      (node (ref "U3") (pin "10") (pinfunction "LED10_10") (pintype "bidirectional"))
    )
    (net (code "38") (name "Net-(U3-REFADJ)") (class "Default")
      (node (ref "R5") (pin "2") (pinfunction "2_2") (pintype "passive"))
      (node (ref "R6") (pin "1") (pinfunction "1_1") (pintype "passive"))
      (node (ref "U3") (pin "8") (pinfunction "REFADJ_8") (pintype "bidirectional"))
    )
    (net (code "39") (name "Net-(U3-REFOUT)") (class "Default")
      (node (ref "R6") (pin "2") (pinfunction "2_2") (pintype "passive"))
      (node (ref "U3") (pin "6") (pinfunction "RHI_6") (pintype "bidirectional"))
      (node (ref "U3") (pin "7") (pinfunction "REFOUT_7") (pintype "bidirectional"))
    )
    (net (code "40") (name "Net-(U3-SIG)") (class "Default")
      (node (ref "J5") (pin "01") (pinfunction "01_01") (pintype "passive"))
      (node (ref "U3") (pin "5") (pinfunction "SIG_5") (pintype "input"))
    )
    (net (code "41") (name "Net-(U4-LED1)") (class "Default")
      (node (ref "D31") (pin "C") (pinfunction "C_C") (pintype "passive"))
      (node (ref "U4") (pin "1") (pinfunction "LED1_1") (pintype "bidirectional"))
    )
    (net (code "42") (name "Net-(U4-LED2)") (class "Default")
      (node (ref "D32") (pin "C") (pinfunction "C_C") (pintype "passive"))
      (node (ref "U4") (pin "18") (pinfunction "LED2_18") (pintype "bidirectional"))
    )
    (net (code "43") (name "Net-(U4-LED3)") (class "Default")
      (node (ref "D33") (pin "C") (pinfunction "C_C") (pintype "passive"))
      (node (ref "U4") (pin "17") (pinfunction "LED3_17") (pintype "bidirectional"))
    )
    (net (code "44") (name "Net-(U4-LED4)") (class "Default")
      (node (ref "D34") (pin "C") (pinfunction "C_C") (pintype "passive"))
      (node (ref "U4") (pin "16") (pinfunction "LED4_16") (pintype "bidirectional"))
    )
    (net (code "45") (name "Net-(U4-LED5)") (class "Default")
      (node (ref "D35") (pin "C") (pinfunction "C_C") (pintype "passive"))
      (node (ref "U4") (pin "15") (pinfunction "LED5_15") (pintype "bidirectional"))
    )
    (net (code "46") (name "Net-(U4-LED6)") (class "Default")
      (node (ref "D36") (pin "C") (pinfunction "C_C") (pintype "passive"))
      (node (ref "U4") (pin "14") (pinfunction "LED6_14") (pintype "bidirectional"))
    )
    (net (code "47") (name "Net-(U4-LED7)") (class "Default")
      (node (ref "D37") (pin "C") (pinfunction "C_C") (pintype "passive"))
      (node (ref "U4") (pin "13") (pinfunction "LED7_13") (pintype "bidirectional"))
    )
    (net (code "48") (name "Net-(U4-LED8)") (class "Default")
      (node (ref "D38") (pin "C") (pinfunction "C_C") (pintype "passive"))
      (node (ref "U4") (pin "12") (pinfunction "LED8_12") (pintype "bidirectional"))
    )
    (net (code "49") (name "Net-(U4-LED9)") (class "Default")
      (node (ref "D39") (pin "C") (pinfunction "C_C") (pintype "passive"))
      (node (ref "U4") (pin "11") (pinfunction "LED9_11") (pintype "bidirectional"))
    )
    (net (code "50") (name "Net-(U4-LED10)") (class "Default")
      (node (ref "D40") (pin "C") (pinfunction "C_C") (pintype "passive"))
      (node (ref "U4") (pin "10") (pinfunction "LED10_10") (pintype "bidirectional"))
    )
    (net (code "51") (name "Net-(U4-REFADJ)") (class "Default")
      (node (ref "R7") (pin "2") (pinfunction "2_2") (pintype "passive"))
      (node (ref "R8") (pin "1") (pinfunction "1_1") (pintype "passive"))
      (node (ref "U4") (pin "8") (pinfunction "REFADJ_8") (pintype "bidirectional"))
    )
    (net (code "52") (name "Net-(U4-REFOUT)") (class "Default")
      (node (ref "R8") (pin "2") (pinfunction "2_2") (pintype "passive"))
      (node (ref "U4") (pin "6") (pinfunction "RHI_6") (pintype "bidirectional"))
      (node (ref "U4") (pin "7") (pinfunction "REFOUT_7") (pintype "bidirectional"))
    )
    (net (code "53") (name "Net-(U4-SIG)") (class "Default")
      (node (ref "J6") (pin "01") (pinfunction "01_01") (pintype "passive"))
      (node (ref "U4") (pin "5") (pinfunction "SIG_5") (pintype "input"))
    )
    (net (code "54") (name "Net-(U5-LED1)") (class "Default")
      (node (ref "D41") (pin "C") (pinfunction "C_C") (pintype "passive"))
      (node (ref "U5") (pin "1") (pinfunction "LED1_1") (pintype "bidirectional"))
    )
    (net (code "55") (name "Net-(U5-LED2)") (class "Default")
      (node (ref "D42") (pin "C") (pinfunction "C_C") (pintype "passive"))
      (node (ref "U5") (pin "18") (pinfunction "LED2_18") (pintype "bidirectional"))
    )
    (net (code "56") (name "Net-(U5-LED3)") (class "Default")
      (node (ref "D43") (pin "C") (pinfunction "C_C") (pintype "passive"))
      (node (ref "U5") (pin "17") (pinfunction "LED3_17") (pintype "bidirectional"))
    )
    (net (code "57") (name "Net-(U5-LED4)") (class "Default")
      (node (ref "D44") (pin "C") (pinfunction "C_C") (pintype "passive"))
      (node (ref "U5") (pin "16") (pinfunction "LED4_16") (pintype "bidirectional"))
    )
    (net (code "58") (name "Net-(U5-LED5)") (class "Default")
      (node (ref "D45") (pin "C") (pinfunction "C_C") (pintype "passive"))
      (node (ref "U5") (pin "15") (pinfunction "LED5_15") (pintype "bidirectional"))
    )
    (net (code "59") (name "Net-(U5-LED6)") (class "Default")
      (node (ref "D46") (pin "C") (pinfunction "C_C") (pintype "passive"))
      (node (ref "U5") (pin "14") (pinfunction "LED6_14") (pintype "bidirectional"))
    )
    (net (code "60") (name "Net-(U5-LED7)") (class "Default")
      (node (ref "D47") (pin "C") (pinfunction "C_C") (pintype "passive"))
      (node (ref "U5") (pin "13") (pinfunction "LED7_13") (pintype "bidirectional"))
    )
    (net (code "61") (name "Net-(U5-LED8)") (class "Default")
      (node (ref "D48") (pin "C") (pinfunction "C_C") (pintype "passive"))
      (node (ref "U5") (pin "12") (pinfunction "LED8_12") (pintype "bidirectional"))
    )
    (net (code "62") (name "Net-(U5-LED9)") (class "Default")
      (node (ref "D49") (pin "C") (pinfunction "C_C") (pintype "passive"))
      (node (ref "U5") (pin "11") (pinfunction "LED9_11") (pintype "bidirectional"))
    )
    (net (code "63") (name "Net-(U5-LED10)") (class "Default")
      (node (ref "D50") (pin "C") (pinfunction "C_C") (pintype "passive"))
      (node (ref "U5") (pin "10") (pinfunction "LED10_10") (pintype "bidirectional"))
    )
    (net (code "64") (name "Net-(U5-REFADJ)") (class "Default")
      (node (ref "R10") (pin "1") (pinfunction "1_1") (pintype "passive"))
      (node (ref "R9") (pin "2") (pinfunction "2_2") (pintype "passive"))
      (node (ref "U5") (pin "8") (pinfunction "REFADJ_8") (pintype "bidirectional"))
    )
    (net (code "65") (name "Net-(U5-REFOUT)") (class "Default")
      (node (ref "R10") (pin "2") (pinfunction "2_2") (pintype "passive"))
      (node (ref "U5") (pin "6") (pinfunction "RHI_6") (pintype "bidirectional"))
      (node (ref "U5") (pin "7") (pinfunction "REFOUT_7") (pintype "bidirectional"))
    )
    (net (code "66") (name "Net-(U5-SIG)") (class "Default")
      (node (ref "J7") (pin "01") (pinfunction "01_01") (pintype "passive"))
      (node (ref "U5") (pin "5") (pinfunction "SIG_5") (pintype "input"))
    )
    (net (code "67") (name "VCC") (class "Default")
      (node (ref "J1") (pin "01") (pinfunction "01_01") (pintype "passive"))
      (node (ref "U1") (pin "3") (pinfunction "V+_3") (pintype "power_in"))
      (node (ref "U1") (pin "9") (pinfunction "MODE_9") (pintype "input"))
      (node (ref "U2") (pin "3") (pinfunction "V+_3") (pintype "power_in"))
      (node (ref "U2") (pin "9") (pinfunction "MODE_9") (pintype "input"))
      (node (ref "U3") (pin "3") (pinfunction "V+_3") (pintype "power_in"))
      (node (ref "U3") (pin "9") (pinfunction "MODE_9") (pintype "input"))
      (node (ref "U4") (pin "3") (pinfunction "V+_3") (pintype "power_in"))
      (node (ref "U4") (pin "9") (pinfunction "MODE_9") (pintype "input"))
      (node (ref "U5") (pin "3") (pinfunction "V+_3") (pintype "power_in"))
      (node (ref "U5") (pin "9") (pinfunction "MODE_9") (pintype "input"))
    )
  )
)
